# EEG-RM_170118P02.net
KiCad netlist of a schematic drawn in EAGLE
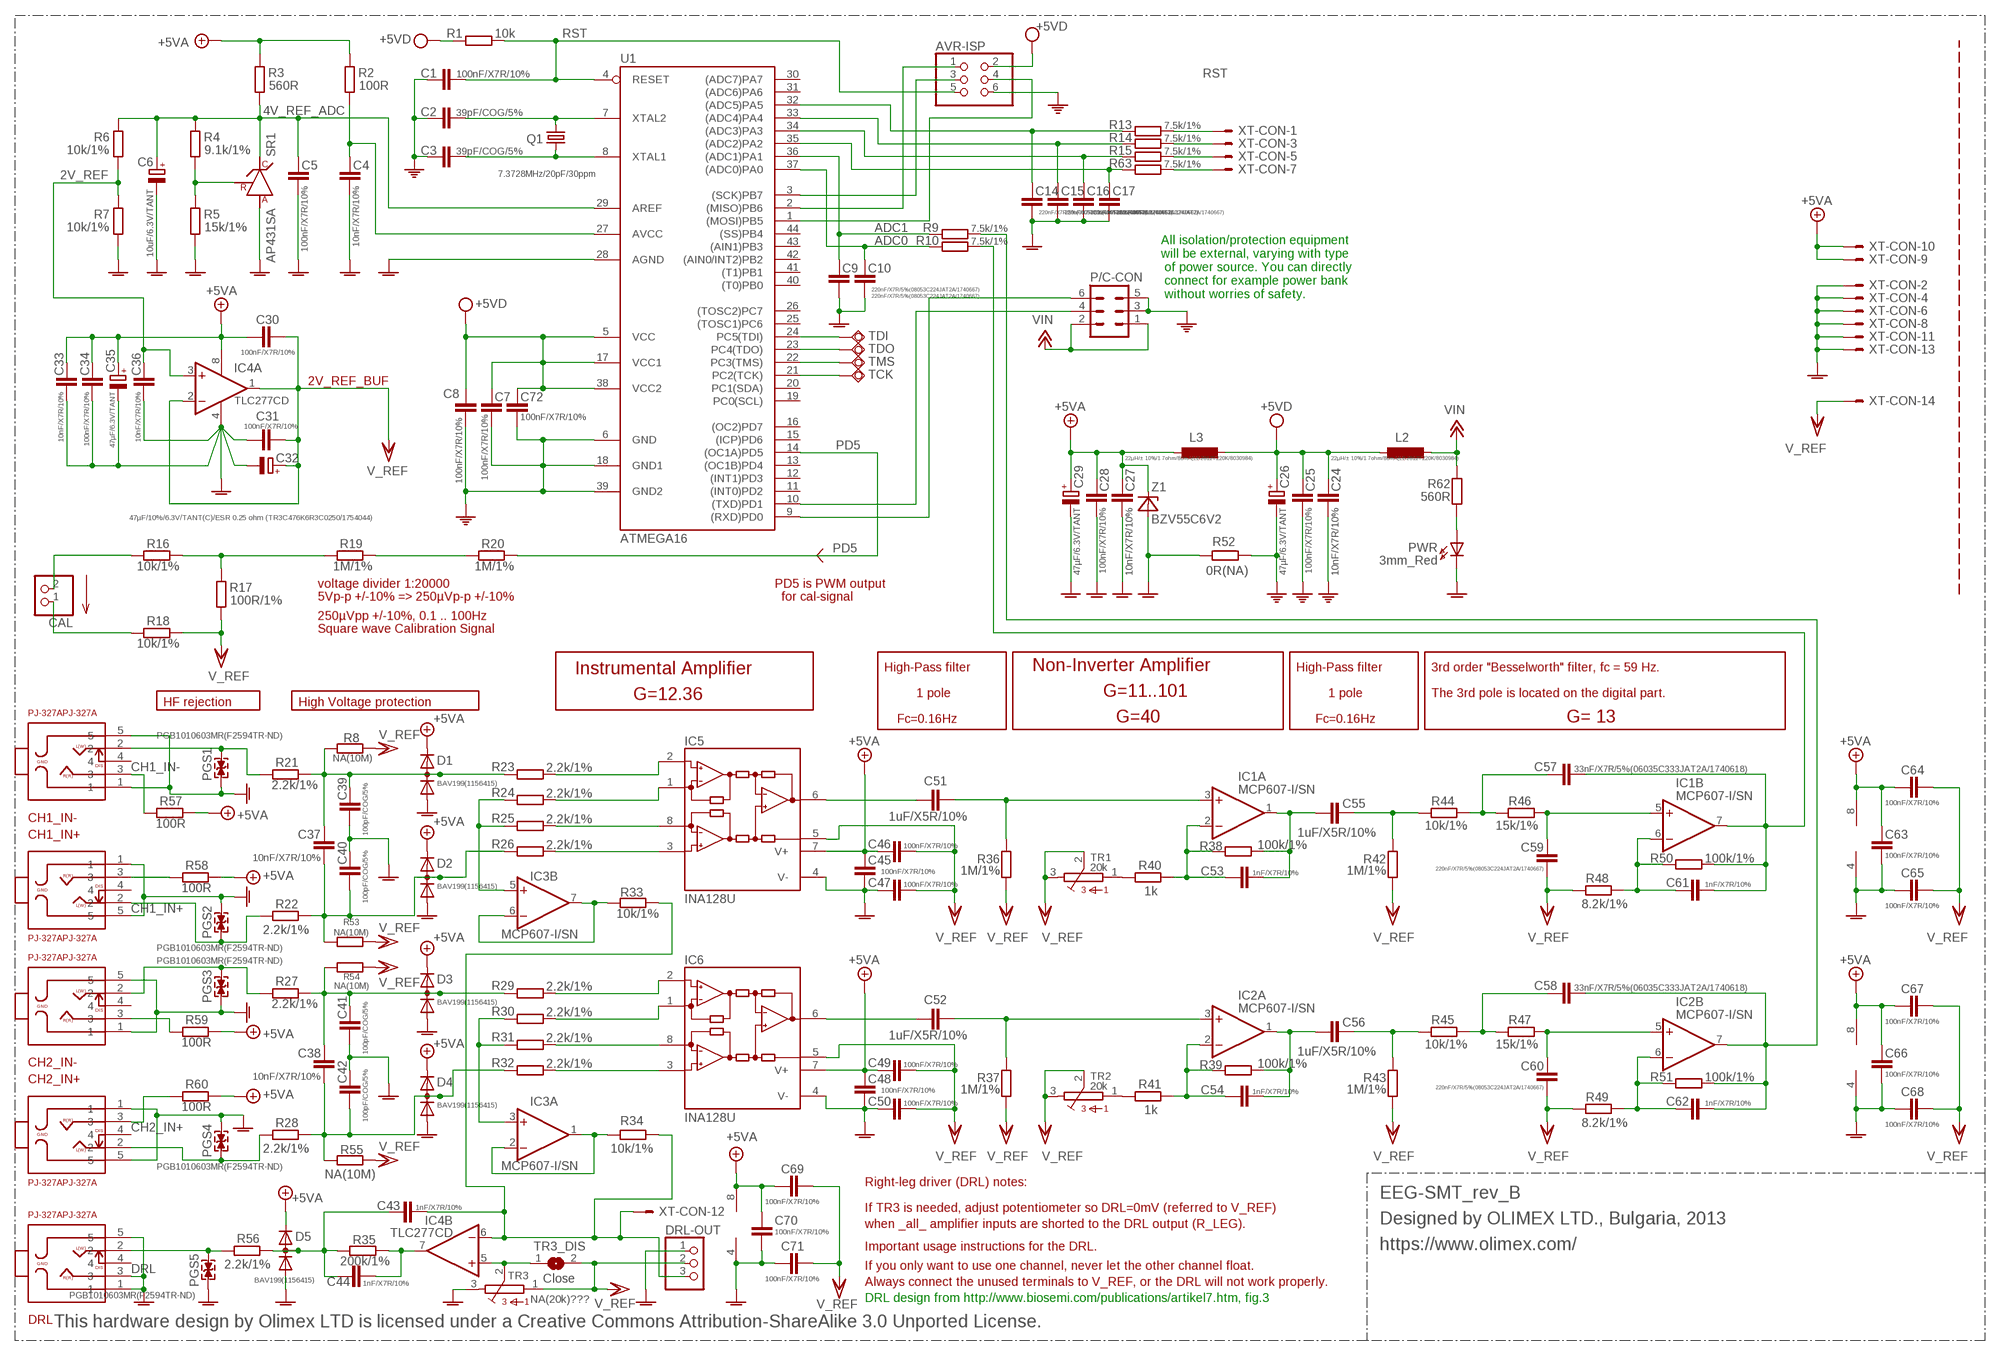
[diagram p0: schematic, sheet 1]

(export (version "E")
  (design (tool "Eeschema 10.0.6"))
  (components
    (comp (ref "AVR-ISP")
      (value "PINHD-2X3")
      (footprint "eagle-import:2X03")
      (libsource (lib "eagle-import") (part "PINHD-2X3"))
    )
    (comp (ref "C1")
      (value "100nF/X7R/10%")
      (footprint "eagle-import:C0603")
      (libsource (lib "eagle-import") (part "C-EUC0603"))
    )
    (comp (ref "C2")
      (value "39pF/COG/5%")
      (footprint "eagle-import:C0603")
      (libsource (lib "eagle-import") (part "C-EUC0603"))
    )
    (comp (ref "C3")
      (value "39pF/COG/5%")
      (footprint "eagle-import:C0603")
      (libsource (lib "eagle-import") (part "C-EUC0603"))
    )
    (comp (ref "C4")
      (value "10nF/X7R/10%")
      (footprint "eagle-import:C0603")
      (libsource (lib "eagle-import") (part "C-EUC0603"))
    )
    (comp (ref "C5")
      (value "100nF/X7R/10%")
      (footprint "eagle-import:C0603")
      (libsource (lib "eagle-import") (part "C-EUC0603"))
    )
    (comp (ref "C6")
      (value "10uF/6.3V/TANT")
      (footprint "eagle-import:CT3216")
      (libsource (lib "eagle-import") (part "CPOL-EUCT3216"))
    )
    (comp (ref "C7")
      (value "100nF/X7R/10%")
      (footprint "eagle-import:C0603")
      (libsource (lib "eagle-import") (part "C-EUC0603"))
    )
    (comp (ref "C8")
      (value "100nF/X7R/10%")
      (footprint "eagle-import:C0603")
      (libsource (lib "eagle-import") (part "C-EUC0603"))
    )
    (comp (ref "C9")
      (value "220nF/X7R/5%(08053C224JAT2A/1740667)")
      (footprint "eagle-import:C0603")
      (libsource (lib "eagle-import") (part "C-EUC0603"))
    )
    (comp (ref "C10")
      (value "220nF/X7R/5%(08053C224JAT2A/1740667)")
      (footprint "eagle-import:C0603")
      (libsource (lib "eagle-import") (part "C-EUC0603"))
    )
    (comp (ref "C14")
      (value "220nF/X7R/5%(08053C224JAT2A/1740667)")
      (footprint "eagle-import:C0603")
      (libsource (lib "eagle-import") (part "C-EUC0603"))
    )
    (comp (ref "C15")
      (value "220nF/X7R/5%(08053C224JAT2A/1740667)")
      (footprint "eagle-import:C0603")
      (libsource (lib "eagle-import") (part "C-EUC0603"))
    )
    (comp (ref "C16")
      (value "220nF/X7R/5%(08053C224JAT2A/1740667)")
      (footprint "eagle-import:C0603")
      (libsource (lib "eagle-import") (part "C-EUC0603"))
    )
    (comp (ref "C17")
      (value "220nF/X7R/5%(08053C224JAT2A/1740667)")
      (footprint "eagle-import:C0603")
      (libsource (lib "eagle-import") (part "C-EUC0603"))
    )
    (comp (ref "C24")
      (value "10nF/X7R/10%")
      (footprint "eagle-import:C0603")
      (libsource (lib "eagle-import") (part "C-EUC0603"))
    )
    (comp (ref "C25")
      (value "100nF/X7R/10%")
      (footprint "eagle-import:C0603")
      (libsource (lib "eagle-import") (part "C-EUC0603"))
    )
    (comp (ref "C26")
      (value "47µF/6.3V/TANT")
      (footprint "eagle-import:CT3216")
      (libsource (lib "eagle-import") (part "CPOL-EUCT3216"))
    )
    (comp (ref "C27")
      (value "10nF/X7R/10%")
      (footprint "eagle-import:C0603")
      (libsource (lib "eagle-import") (part "C-EUC0603"))
    )
    (comp (ref "C28")
      (value "100nF/X7R/10%")
      (footprint "eagle-import:C0603")
      (libsource (lib "eagle-import") (part "C-EUC0603"))
    )
    (comp (ref "C29")
      (value "47µF/6.3V/TANT")
      (footprint "eagle-import:CT3216")
      (libsource (lib "eagle-import") (part "CPOL-EUCT3216"))
    )
    (comp (ref "C30")
      (value "100nF/X7R/10%")
      (footprint "eagle-import:C0603")
      (libsource (lib "eagle-import") (part "C-EUC0603"))
    )
    (comp (ref "C31")
      (value "100nF/X7R/10%")
      (footprint "eagle-import:C0603")
      (libsource (lib "eagle-import") (part "C-EUC0603"))
    )
    (comp (ref "C32")
      (value "47µF/10%/6.3V/TANT(C)/ESR 0.25 ohm (TR3C476K6R3C0250/1754044)")
      (footprint "eagle-import:CT3528")
      (libsource (lib "eagle-import") (part "CPOL-EUCT3528"))
    )
    (comp (ref "C33")
      (value "10nF/X7R/10%")
      (footprint "eagle-import:C0603")
      (libsource (lib "eagle-import") (part "C-EUC0603"))
    )
    (comp (ref "C34")
      (value "100nF/X7R/10%")
      (footprint "eagle-import:C0603")
      (libsource (lib "eagle-import") (part "C-EUC0603"))
    )
    (comp (ref "C35")
      (value "47µF/6.3V/TANT")
      (footprint "eagle-import:CT3216")
      (libsource (lib "eagle-import") (part "CPOL-EUCT3216"))
    )
    (comp (ref "C36")
      (value "10nF/X7R/10%")
      (footprint "eagle-import:C0603")
      (libsource (lib "eagle-import") (part "C-EUC0603"))
    )
    (comp (ref "C37")
      (value "10nF/X7R/10%")
      (footprint "eagle-import:C0603")
      (libsource (lib "eagle-import") (part "C-EUC0603"))
    )
    (comp (ref "C38")
      (value "10nF/X7R/10%")
      (footprint "eagle-import:C0603")
      (libsource (lib "eagle-import") (part "C-EUC0603"))
    )
    (comp (ref "C39")
      (value "100pF/COG/5%")
      (footprint "eagle-import:C0603")
      (libsource (lib "eagle-import") (part "C-EUC0603"))
    )
    (comp (ref "C40")
      (value "100pF/COG/5%")
      (footprint "eagle-import:C0603")
      (libsource (lib "eagle-import") (part "C-EUC0603"))
    )
    (comp (ref "C41")
      (value "100pF/COG/5%")
      (footprint "eagle-import:C0603")
      (libsource (lib "eagle-import") (part "C-EUC0603"))
    )
    (comp (ref "C42")
      (value "100pF/COG/5%")
      (footprint "eagle-import:C0603")
      (libsource (lib "eagle-import") (part "C-EUC0603"))
    )
    (comp (ref "C43")
      (value "1nF/X7R/10%")
      (footprint "eagle-import:C0603")
      (libsource (lib "eagle-import") (part "C-EUC0603"))
    )
    (comp (ref "C44")
      (value "1nF/X7R/10%")
      (footprint "eagle-import:C0603")
      (libsource (lib "eagle-import") (part "C-EUC0603"))
    )
    (comp (ref "C45")
      (value "100nF/X7R/10%")
      (footprint "eagle-import:C0603")
      (libsource (lib "eagle-import") (part "C-EUC0603"))
    )
    (comp (ref "C46")
      (value "100nF/X7R/10%")
      (footprint "eagle-import:C0603")
      (libsource (lib "eagle-import") (part "C-EUC0603"))
    )
    (comp (ref "C47")
      (value "100nF/X7R/10%")
      (footprint "eagle-import:C0603")
      (libsource (lib "eagle-import") (part "C-EUC0603"))
    )
    (comp (ref "C48")
      (value "100nF/X7R/10%")
      (footprint "eagle-import:C0603")
      (libsource (lib "eagle-import") (part "C-EUC0603"))
    )
    (comp (ref "C49")
      (value "100nF/X7R/10%")
      (footprint "eagle-import:C0603")
      (libsource (lib "eagle-import") (part "C-EUC0603"))
    )
    (comp (ref "C50")
      (value "100nF/X7R/10%")
      (footprint "eagle-import:C0603")
      (libsource (lib "eagle-import") (part "C-EUC0603"))
    )
    (comp (ref "C51")
      (value "1uF/X5R/10%")
      (footprint "eagle-import:C0603")
      (libsource (lib "eagle-import") (part "C-EUC0603"))
    )
    (comp (ref "C52")
      (value "1uF/X5R/10%")
      (footprint "eagle-import:C0603")
      (libsource (lib "eagle-import") (part "C-EUC0603"))
    )
    (comp (ref "C53")
      (value "1nF/X7R/10%")
      (footprint "eagle-import:C0603")
      (libsource (lib "eagle-import") (part "C-EUC0603"))
    )
    (comp (ref "C54")
      (value "1nF/X7R/10%")
      (footprint "eagle-import:C0603")
      (libsource (lib "eagle-import") (part "C-EUC0603"))
    )
    (comp (ref "C55")
      (value "1uF/X5R/10%")
      (footprint "eagle-import:C0603")
      (libsource (lib "eagle-import") (part "C-EUC0603"))
    )
    (comp (ref "C56")
      (value "1uF/X5R/10%")
      (footprint "eagle-import:C0603")
      (libsource (lib "eagle-import") (part "C-EUC0603"))
    )
    (comp (ref "C57")
      (value "33nF/X7R/5%(06035C333JAT2A/1740618)")
      (footprint "eagle-import:C0603")
      (libsource (lib "eagle-import") (part "C-EUC0603"))
    )
    (comp (ref "C58")
      (value "33nF/X7R/5%(06035C333JAT2A/1740618)")
      (footprint "eagle-import:C0603")
      (libsource (lib "eagle-import") (part "C-EUC0603"))
    )
    (comp (ref "C59")
      (value "220nF/X7R/5%(08053C224JAT2A/1740667)")
      (footprint "eagle-import:C0603")
      (libsource (lib "eagle-import") (part "C-EUC0603"))
    )
    (comp (ref "C60")
      (value "220nF/X7R/5%(08053C224JAT2A/1740667)")
      (footprint "eagle-import:C0603")
      (libsource (lib "eagle-import") (part "C-EUC0603"))
    )
    (comp (ref "C61")
      (value "1nF/X7R/10%")
      (footprint "eagle-import:C0603")
      (libsource (lib "eagle-import") (part "C-EUC0603"))
    )
    (comp (ref "C62")
      (value "1nF/X7R/10%")
      (footprint "eagle-import:C0603")
      (libsource (lib "eagle-import") (part "C-EUC0603"))
    )
    (comp (ref "C63")
      (value "100nF/X7R/10%")
      (footprint "eagle-import:C0603")
      (libsource (lib "eagle-import") (part "C-EUC0603"))
    )
    (comp (ref "C64")
      (value "100nF/X7R/10%")
      (footprint "eagle-import:C0603")
      (libsource (lib "eagle-import") (part "C-EUC0603"))
    )
    (comp (ref "C65")
      (value "100nF/X7R/10%")
      (footprint "eagle-import:C0603")
      (libsource (lib "eagle-import") (part "C-EUC0603"))
    )
    (comp (ref "C66")
      (value "100nF/X7R/10%")
      (footprint "eagle-import:C0603")
      (libsource (lib "eagle-import") (part "C-EUC0603"))
    )
    (comp (ref "C67")
      (value "100nF/X7R/10%")
      (footprint "eagle-import:C0603")
      (libsource (lib "eagle-import") (part "C-EUC0603"))
    )
    (comp (ref "C68")
      (value "100nF/X7R/10%")
      (footprint "eagle-import:C0603")
      (libsource (lib "eagle-import") (part "C-EUC0603"))
    )
    (comp (ref "C69")
      (value "100nF/X7R/10%")
      (footprint "eagle-import:C0603")
      (libsource (lib "eagle-import") (part "C-EUC0603"))
    )
    (comp (ref "C70")
      (value "100nF/X7R/10%")
      (footprint "eagle-import:C0603")
      (libsource (lib "eagle-import") (part "C-EUC0603"))
    )
    (comp (ref "C71")
      (value "100nF/X7R/10%")
      (footprint "eagle-import:C0603")
      (libsource (lib "eagle-import") (part "C-EUC0603"))
    )
    (comp (ref "C72")
      (value "100nF/X7R/10%")
      (footprint "eagle-import:C0603")
      (libsource (lib "eagle-import") (part "C-EUC0603"))
    )
    (comp (ref "CAL")
      (value "PINHD-1X2")
      (footprint "eagle-import:1X02")
      (libsource (lib "eagle-import") (part "PINHD-1X2"))
    )
    (comp (ref "CH1_IN+")
      (value "PJ-327APJ-327A")
      (footprint "eagle-import:PJ-327A")
      (libsource (lib "eagle-import") (part "PJ-327APJ-327A"))
    )
    (comp (ref "CH1_IN-")
      (value "PJ-327APJ-327A")
      (footprint "eagle-import:PJ-327A")
      (libsource (lib "eagle-import") (part "PJ-327APJ-327A"))
    )
    (comp (ref "CH2_IN+")
      (value "PJ-327APJ-327A")
      (footprint "eagle-import:PJ-327A")
      (libsource (lib "eagle-import") (part "PJ-327APJ-327A"))
    )
    (comp (ref "CH2_IN-")
      (value "PJ-327APJ-327A")
      (footprint "eagle-import:PJ-327A")
      (libsource (lib "eagle-import") (part "PJ-327APJ-327A"))
    )
    (comp (ref "D1")
      (value "BAV199(1156415)")
      (footprint "eagle-import:SOT23C")
      (libsource (lib "eagle-import") (part "DIODE_AC-AC__"))
    )
    (comp (ref "D2")
      (value "BAV199(1156415)")
      (footprint "eagle-import:SOT23C")
      (libsource (lib "eagle-import") (part "DIODE_AC-AC__"))
    )
    (comp (ref "D3")
      (value "BAV199(1156415)")
      (footprint "eagle-import:SOT23C")
      (libsource (lib "eagle-import") (part "DIODE_AC-AC__"))
    )
    (comp (ref "D4")
      (value "BAV199(1156415)")
      (footprint "eagle-import:SOT23C")
      (libsource (lib "eagle-import") (part "DIODE_AC-AC__"))
    )
    (comp (ref "D5")
      (value "BAV199(1156415)")
      (footprint "eagle-import:SOT23C")
      (libsource (lib "eagle-import") (part "DIODE_AC-AC__"))
    )
    (comp (ref "DRL")
      (value "PJ-327APJ-327A")
      (footprint "eagle-import:PJ-327A")
      (libsource (lib "eagle-import") (part "PJ-327APJ-327A"))
    )
    (comp (ref "DRL-OUT")
      (value "PINHD-1X3")
      (footprint "eagle-import:1X03")
      (libsource (lib "eagle-import") (part "PINHD-1X3"))
    )
    (comp (ref "IC1")
      (value "MCP607-I/SN")
      (footprint "eagle-import:SO08")
      (libsource (lib "eagle-import") (part "LM358D"))
    )
    (comp (ref "IC2")
      (value "MCP607-I/SN")
      (footprint "eagle-import:SO08")
      (libsource (lib "eagle-import") (part "LM358D"))
    )
    (comp (ref "IC3")
      (value "MCP607-I/SN")
      (footprint "eagle-import:SO08")
      (libsource (lib "eagle-import") (part "LM358D"))
    )
    (comp (ref "IC4")
      (value "TLC277CD")
      (footprint "eagle-import:SO08")
      (libsource (lib "eagle-import") (part "LM358D"))
    )
    (comp (ref "IC5")
      (value "INA128U")
      (footprint "eagle-import:SO08")
      (fields (field (name "MF") "TEXAS INSTRUMENTS"))
      (libsource (lib "eagle-import") (part "INA128U"))
    )
    (comp (ref "IC6")
      (value "INA128U")
      (footprint "eagle-import:SO08")
      (fields (field (name "MF") "TEXAS INSTRUMENTS"))
      (libsource (lib "eagle-import") (part "INA128U"))
    )
    (comp (ref "L2")
      (value "22µH/± 10%/1.7ohm/80mA(LB2012T220K/8030984)")
      (footprint "eagle-import:L2012C")
      (libsource (lib "eagle-import") (part "L-EUL2012C"))
    )
    (comp (ref "L3")
      (value "22µH/± 10%/1.7ohm/80mA(LB2012T220K/8030984)")
      (footprint "eagle-import:L2012C")
      (libsource (lib "eagle-import") (part "L-EUL2012C"))
    )
    (comp (ref "P/C-CON")
      (value "ML6L")
      (footprint "eagle-import:ML6L")
      (libsource (lib "eagle-import") (part "ML6L"))
    )
    (comp (ref "PGS1")
      (value "PGB1010603MR(F2594TR-ND)")
      (footprint "eagle-import:0603")
      (libsource (lib "eagle-import") (part "PGB1010603MR(F2594TR-ND)"))
    )
    (comp (ref "PGS2")
      (value "PGB1010603MR(F2594TR-ND)")
      (footprint "eagle-import:0603")
      (libsource (lib "eagle-import") (part "PGB1010603MR(F2594TR-ND)"))
    )
    (comp (ref "PGS3")
      (value "PGB1010603MR(F2594TR-ND)")
      (footprint "eagle-import:0603")
      (libsource (lib "eagle-import") (part "PGB1010603MR(F2594TR-ND)"))
    )
    (comp (ref "PGS4")
      (value "PGB1010603MR(F2594TR-ND)")
      (footprint "eagle-import:0603")
      (libsource (lib "eagle-import") (part "PGB1010603MR(F2594TR-ND)"))
    )
    (comp (ref "PGS5")
      (value "PGB1010603MR(F2594TR-ND)")
      (footprint "eagle-import:0603")
      (libsource (lib "eagle-import") (part "PGB1010603MR(F2594TR-ND)"))
    )
    (comp (ref "PWR")
      (value "3mm_Red")
      (footprint "eagle-import:LED-3.0MM")
      (libsource (lib "eagle-import") (part "LED3.0MM"))
    )
    (comp (ref "Q1")
      (value "7.3728MHz/20pF/30ppm")
      (footprint "eagle-import:HC49_SMD2_THIN")
      (libsource (lib "eagle-import") (part "HC49/S1"))
    )
    (comp (ref "R1")
      (value "10k")
      (footprint "eagle-import:R0603")
      (libsource (lib "eagle-import") (part "R-EU_R0603"))
    )
    (comp (ref "R2")
      (value "100R")
      (footprint "eagle-import:R0603")
      (libsource (lib "eagle-import") (part "R-EU_R0603"))
    )
    (comp (ref "R3")
      (value "560R")
      (footprint "eagle-import:R0603")
      (libsource (lib "eagle-import") (part "R-EU_R0603"))
    )
    (comp (ref "R4")
      (value "9.1k/1%")
      (footprint "eagle-import:R0603")
      (libsource (lib "eagle-import") (part "R-EU_R0603"))
    )
    (comp (ref "R5")
      (value "15k/1%")
      (footprint "eagle-import:R0603")
      (libsource (lib "eagle-import") (part "R-EU_R0603"))
    )
    (comp (ref "R6")
      (value "10k/1%")
      (footprint "eagle-import:R0603")
      (libsource (lib "eagle-import") (part "R-EU_R0603"))
    )
    (comp (ref "R7")
      (value "10k/1%")
      (footprint "eagle-import:R0603")
      (libsource (lib "eagle-import") (part "R-EU_R0603"))
    )
    (comp (ref "R8")
      (value "NA(10M)")
      (footprint "eagle-import:R0603")
      (libsource (lib "eagle-import") (part "R-EU_R0603"))
    )
    (comp (ref "R9")
      (value "7.5k/1%")
      (footprint "eagle-import:M2012")
      (libsource (lib "eagle-import") (part "R-EU_M2012"))
    )
    (comp (ref "R10")
      (value "7.5k/1%")
      (footprint "eagle-import:M2012")
      (libsource (lib "eagle-import") (part "R-EU_M2012"))
    )
    (comp (ref "R13")
      (value "7.5k/1%")
      (footprint "eagle-import:M2012")
      (libsource (lib "eagle-import") (part "R-EU_M2012"))
    )
    (comp (ref "R14")
      (value "7.5k/1%")
      (footprint "eagle-import:M2012")
      (libsource (lib "eagle-import") (part "R-EU_M2012"))
    )
    (comp (ref "R15")
      (value "7.5k/1%")
      (footprint "eagle-import:M2012")
      (libsource (lib "eagle-import") (part "R-EU_M2012"))
    )
    (comp (ref "R16")
      (value "10k/1%")
      (footprint "eagle-import:R0603")
      (libsource (lib "eagle-import") (part "R-EU_R0603"))
    )
    (comp (ref "R17")
      (value "100R/1%")
      (footprint "eagle-import:R0603")
      (libsource (lib "eagle-import") (part "R-EU_R0603"))
    )
    (comp (ref "R18")
      (value "10k/1%")
      (footprint "eagle-import:R0603")
      (libsource (lib "eagle-import") (part "R-EU_R0603"))
    )
    (comp (ref "R19")
      (value "1M/1%")
      (footprint "eagle-import:R0603")
      (libsource (lib "eagle-import") (part "R-EU_R0603"))
    )
    (comp (ref "R20")
      (value "1M/1%")
      (footprint "eagle-import:R0603")
      (libsource (lib "eagle-import") (part "R-EU_R0603"))
    )
    (comp (ref "R21")
      (value "2.2k/1%")
      (footprint "eagle-import:R0603")
      (libsource (lib "eagle-import") (part "R-EU_R0603"))
    )
    (comp (ref "R22")
      (value "2.2k/1%")
      (footprint "eagle-import:R0603")
      (libsource (lib "eagle-import") (part "R-EU_R0603"))
    )
    (comp (ref "R23")
      (value "2.2k/1%")
      (footprint "eagle-import:R0603")
      (libsource (lib "eagle-import") (part "R-EU_R0603"))
    )
    (comp (ref "R24")
      (value "2.2k/1%")
      (footprint "eagle-import:R0603")
      (libsource (lib "eagle-import") (part "R-EU_R0603"))
    )
    (comp (ref "R25")
      (value "2.2k/1%")
      (footprint "eagle-import:R0603")
      (libsource (lib "eagle-import") (part "R-EU_R0603"))
    )
    (comp (ref "R26")
      (value "2.2k/1%")
      (footprint "eagle-import:R0603")
      (libsource (lib "eagle-import") (part "R-EU_R0603"))
    )
    (comp (ref "R27")
      (value "2.2k/1%")
      (footprint "eagle-import:R0603")
      (libsource (lib "eagle-import") (part "R-EU_R0603"))
    )
    (comp (ref "R28")
      (value "2.2k/1%")
      (footprint "eagle-import:R0603")
      (libsource (lib "eagle-import") (part "R-EU_R0603"))
    )
    (comp (ref "R29")
      (value "2.2k/1%")
      (footprint "eagle-import:R0603")
      (libsource (lib "eagle-import") (part "R-EU_R0603"))
    )
    (comp (ref "R30")
      (value "2.2k/1%")
      (footprint "eagle-import:R0603")
      (libsource (lib "eagle-import") (part "R-EU_R0603"))
    )
    (comp (ref "R31")
      (value "2.2k/1%")
      (footprint "eagle-import:R0603")
      (libsource (lib "eagle-import") (part "R-EU_R0603"))
    )
    (comp (ref "R32")
      (value "2.2k/1%")
      (footprint "eagle-import:R0603")
      (libsource (lib "eagle-import") (part "R-EU_R0603"))
    )
    (comp (ref "R33")
      (value "10k/1%")
      (footprint "eagle-import:R0603")
      (libsource (lib "eagle-import") (part "R-EU_R0603"))
    )
    (comp (ref "R34")
      (value "10k/1%")
      (footprint "eagle-import:R0603")
      (libsource (lib "eagle-import") (part "R-EU_R0603"))
    )
    (comp (ref "R35")
      (value "200k/1%")
      (footprint "eagle-import:R0603")
      (libsource (lib "eagle-import") (part "R-EU_R0603"))
    )
    (comp (ref "R36")
      (value "1M/1%")
      (footprint "eagle-import:R0603")
      (libsource (lib "eagle-import") (part "R-EU_R0603"))
    )
    (comp (ref "R37")
      (value "1M/1%")
      (footprint "eagle-import:R0603")
      (libsource (lib "eagle-import") (part "R-EU_R0603"))
    )
    (comp (ref "R38")
      (value "100k/1%")
      (footprint "eagle-import:R0603")
      (libsource (lib "eagle-import") (part "R-EU_R0603"))
    )
    (comp (ref "R39")
      (value "100k/1%")
      (footprint "eagle-import:R0603")
      (libsource (lib "eagle-import") (part "R-EU_R0603"))
    )
    (comp (ref "R40")
      (value "1k")
      (footprint "eagle-import:R0603")
      (libsource (lib "eagle-import") (part "R-EU_R0603"))
    )
    (comp (ref "R41")
      (value "1k")
      (footprint "eagle-import:R0603")
      (libsource (lib "eagle-import") (part "R-EU_R0603"))
    )
    (comp (ref "R42")
      (value "1M/1%")
      (footprint "eagle-import:R0603")
      (libsource (lib "eagle-import") (part "R-EU_R0603"))
    )
    (comp (ref "R43")
      (value "1M/1%")
      (footprint "eagle-import:R0603")
      (libsource (lib "eagle-import") (part "R-EU_R0603"))
    )
    (comp (ref "R44")
      (value "10k/1%")
      (footprint "eagle-import:R0603")
      (libsource (lib "eagle-import") (part "R-EU_R0603"))
    )
    (comp (ref "R45")
      (value "10k/1%")
      (footprint "eagle-import:R0603")
      (libsource (lib "eagle-import") (part "R-EU_R0603"))
    )
    (comp (ref "R46")
      (value "15k/1%")
      (footprint "eagle-import:R0603")
      (libsource (lib "eagle-import") (part "R-EU_R0603"))
    )
    (comp (ref "R47")
      (value "15k/1%")
      (footprint "eagle-import:R0603")
      (libsource (lib "eagle-import") (part "R-EU_R0603"))
    )
    (comp (ref "R48")
      (value "8.2k/1%")
      (footprint "eagle-import:R0603")
      (libsource (lib "eagle-import") (part "R-EU_R0603"))
    )
    (comp (ref "R49")
      (value "8.2k/1%")
      (footprint "eagle-import:R0603")
      (libsource (lib "eagle-import") (part "R-EU_R0603"))
    )
    (comp (ref "R50")
      (value "100k/1%")
      (footprint "eagle-import:R0603")
      (libsource (lib "eagle-import") (part "R-EU_R0603"))
    )
    (comp (ref "R51")
      (value "100k/1%")
      (footprint "eagle-import:R0603")
      (libsource (lib "eagle-import") (part "R-EU_R0603"))
    )
    (comp (ref "R52")
      (value "0R(NA)")
      (footprint "eagle-import:R0603")
      (libsource (lib "eagle-import") (part "R-EU_R0603"))
    )
    (comp (ref "R53")
      (value "NA(10M)")
      (footprint "eagle-import:R0603")
      (libsource (lib "eagle-import") (part "R-EU_R0603"))
    )
    (comp (ref "R54")
      (value "NA(10M)")
      (footprint "eagle-import:R0603")
      (libsource (lib "eagle-import") (part "R-EU_R0603"))
    )
    (comp (ref "R55")
      (value "NA(10M)")
      (footprint "eagle-import:R0603")
      (libsource (lib "eagle-import") (part "R-EU_R0603"))
    )
    (comp (ref "R56")
      (value "2.2k/1%")
      (footprint "eagle-import:R0603")
      (libsource (lib "eagle-import") (part "R-EU_R0603"))
    )
    (comp (ref "R57")
      (value "100R")
      (footprint "eagle-import:R0603")
      (libsource (lib "eagle-import") (part "R-EU_R0603"))
    )
    (comp (ref "R58")
      (value "100R")
      (footprint "eagle-import:R0603")
      (libsource (lib "eagle-import") (part "R-EU_R0603"))
    )
    (comp (ref "R59")
      (value "100R")
      (footprint "eagle-import:R0603")
      (libsource (lib "eagle-import") (part "R-EU_R0603"))
    )
    (comp (ref "R60")
      (value "100R")
      (footprint "eagle-import:R0603")
      (libsource (lib "eagle-import") (part "R-EU_R0603"))
    )
    (comp (ref "R62")
      (value "560R")
      (footprint "eagle-import:R0603")
      (libsource (lib "eagle-import") (part "R-EU_R0603"))
    )
    (comp (ref "R63")
      (value "7.5k/1%")
      (footprint "eagle-import:M2012")
      (libsource (lib "eagle-import") (part "R-EU_M2012"))
    )
    (comp (ref "SR1")
      (value "AP431SA")
      (footprint "eagle-import:SOT-23")
      (libsource (lib "eagle-import") (part "TL431'''"))
    )
    (comp (ref "TCK")
      (value "TESTPAD80/30")
      (footprint "eagle-import:SMD80_30")
      (libsource (lib "eagle-import") (part "TESTPAD80/30"))
    )
    (comp (ref "TDI")
      (value "TESTPAD80/30")
      (footprint "eagle-import:SMD80_30")
      (libsource (lib "eagle-import") (part "TESTPAD80/30"))
    )
    (comp (ref "TDO")
      (value "TESTPAD80/30")
      (footprint "eagle-import:SMD80_30")
      (libsource (lib "eagle-import") (part "TESTPAD80/30"))
    )
    (comp (ref "TMS")
      (value "TESTPAD80/30")
      (footprint "eagle-import:SMD80_30")
      (libsource (lib "eagle-import") (part "TESTPAD80/30"))
    )
    (comp (ref "TR1")
      (value "20k")
      (footprint "eagle-import:S64Y")
      (libsource (lib "eagle-import") (part "S64Y"))
    )
    (comp (ref "TR2")
      (value "20k")
      (footprint "eagle-import:S64Y")
      (libsource (lib "eagle-import") (part "S64Y"))
    )
    (comp (ref "TR3")
      (value "NA(20k)???")
      (footprint "eagle-import:S64Y")
      (libsource (lib "eagle-import") (part "S64Y"))
    )
    (comp (ref "TR3_DIS")
      (value "Close")
      (footprint "eagle-import:SJ_1_SMALLER")
      (libsource (lib "eagle-import") (part "SJSJ_SMALLER"))
    )
    (comp (ref "U1")
      (value "ATMEGA16")
      (footprint "eagle-import:44TQFP")
      (libsource (lib "eagle-import") (part "ATMEGA16"))
    )
    (comp (ref "XT-CON")
      (value "ML14LE")
      (footprint "eagle-import:ML14L")
      (libsource (lib "eagle-import") (part "ML14?EL"))
    )
    (comp (ref "Z1")
      (value "BZV55C6V2")
      (footprint "eagle-import:MINI-MELF")
      (libsource (lib "eagle-import") (part "ZDIOD-SMD"))
    )
  )
  (nets
    (net (code "1") (name "+5VA") (class "Default")
      (node (ref "C27") (pin "1") (pinfunction "1_1") (pintype "passive"))
      (node (ref "C28") (pin "1") (pinfunction "1_1") (pintype "passive"))
      (node (ref "C29") (pin "+") (pinfunction "+_+") (pintype "passive"))
      (node (ref "C30") (pin "2") (pinfunction "2_2") (pintype "passive"))
      (node (ref "C33") (pin "1") (pinfunction "1_1") (pintype "passive"))
      (node (ref "C34") (pin "1") (pinfunction "1_1") (pintype "passive"))
      (node (ref "C35") (pin "+") (pinfunction "+_+") (pintype "passive"))
      (node (ref "C45") (pin "1") (pinfunction "1_1") (pintype "passive"))
      (node (ref "C46") (pin "1") (pinfunction "1_1") (pintype "passive"))
      (node (ref "C48") (pin "1") (pinfunction "1_1") (pintype "passive"))
      (node (ref "C49") (pin "1") (pinfunction "1_1") (pintype "passive"))
      (node (ref "C63") (pin "1") (pinfunction "1_1") (pintype "passive"))
      (node (ref "C64") (pin "1") (pinfunction "1_1") (pintype "passive"))
      (node (ref "C66") (pin "1") (pinfunction "1_1") (pintype "passive"))
      (node (ref "C67") (pin "1") (pinfunction "1_1") (pintype "passive"))
      (node (ref "C69") (pin "1") (pinfunction "1_1") (pintype "passive"))
      (node (ref "C70") (pin "1") (pinfunction "1_1") (pintype "passive"))
      (node (ref "D1") (pin "1") (pinfunction "K_1") (pintype "passive"))
      (node (ref "D2") (pin "1") (pinfunction "K_1") (pintype "passive"))
      (node (ref "D3") (pin "1") (pinfunction "K_1") (pintype "passive"))
      (node (ref "D4") (pin "1") (pinfunction "K_1") (pintype "passive"))
      (node (ref "D5") (pin "1") (pinfunction "K_1") (pintype "passive"))
      (node (ref "IC1") (pin "8") (pinfunction "V+_8") (pintype "power_in"))
      (node (ref "IC2") (pin "8") (pinfunction "V+_8") (pintype "power_in"))
      (node (ref "IC3") (pin "8") (pinfunction "V+_8") (pintype "power_in"))
      (node (ref "IC4") (pin "8") (pinfunction "V+_8") (pintype "power_in"))
      (node (ref "IC5") (pin "7") (pinfunction "V+_7") (pintype "power_in"))
      (node (ref "IC6") (pin "7") (pinfunction "V+_7") (pintype "power_in"))
      (node (ref "L3") (pin "2") (pinfunction "2_2") (pintype "passive"))
      (node (ref "R2") (pin "2") (pinfunction "2_2") (pintype "passive"))
      (node (ref "R3") (pin "2") (pinfunction "2_2") (pintype "passive"))
      (node (ref "R57") (pin "2") (pinfunction "2_2") (pintype "passive"))
      (node (ref "R58") (pin "2") (pinfunction "2_2") (pintype "passive"))
      (node (ref "R59") (pin "2") (pinfunction "2_2") (pintype "passive"))
      (node (ref "R60") (pin "2") (pinfunction "2_2") (pintype "passive"))
      (node (ref "XT-CON") (pin "10") (pinfunction "S_10") (pintype "passive"))
      (node (ref "XT-CON") (pin "9") (pinfunction "S_9") (pintype "passive"))
      (node (ref "Z1") (pin "1") (pinfunction "C_1") (pintype "passive"))
    )
    (net (code "2") (name "+5VD") (class "Default")
      (node (ref "AVR-ISP") (pin "2") (pinfunction "2_2") (pintype "passive"))
      (node (ref "C24") (pin "1") (pinfunction "1_1") (pintype "passive"))
      (node (ref "C25") (pin "1") (pinfunction "1_1") (pintype "passive"))
      (node (ref "C26") (pin "+") (pinfunction "+_+") (pintype "passive"))
      (node (ref "C7") (pin "1") (pinfunction "1_1") (pintype "passive"))
      (node (ref "C72") (pin "1") (pinfunction "1_1") (pintype "passive"))
      (node (ref "C8") (pin "1") (pinfunction "1_1") (pintype "passive"))
      (node (ref "L2") (pin "2") (pinfunction "2_2") (pintype "passive"))
      (node (ref "L3") (pin "1") (pinfunction "1_1") (pintype "passive"))
      (node (ref "R1") (pin "1") (pinfunction "1_1") (pintype "passive"))
      (node (ref "U1") (pin "17") (pinfunction "VCC1_17") (pintype "bidirectional"))
      (node (ref "U1") (pin "38") (pinfunction "VCC2_38") (pintype "bidirectional"))
      (node (ref "U1") (pin "5") (pinfunction "VCC_5") (pintype "power_in"))
    )
    (net (code "3") (name "/2V_REF") (class "Default")
      (node (ref "C36") (pin "1") (pinfunction "1_1") (pintype "passive"))
      (node (ref "IC4") (pin "3") (pinfunction "+IN_3") (pintype "input"))
      (node (ref "R6") (pin "1") (pinfunction "1_1") (pintype "passive"))
      (node (ref "R7") (pin "2") (pinfunction "2_2") (pintype "passive"))
    )
    (net (code "4") (name "/4V_REF_ADC") (class "Default")
      (node (ref "C5") (pin "1") (pinfunction "1_1") (pintype "passive"))
      (node (ref "C6") (pin "+") (pinfunction "+_+") (pintype "passive"))
      (node (ref "R3") (pin "1") (pinfunction "1_1") (pintype "passive"))
      (node (ref "R4") (pin "2") (pinfunction "2_2") (pintype "passive"))
      (node (ref "R6") (pin "2") (pinfunction "2_2") (pintype "passive"))
      (node (ref "SR1") (pin "1") (pinfunction "C_1") (pintype "input"))
      (node (ref "U1") (pin "29") (pinfunction "AREF_29") (pintype "power_in"))
    )
    (net (code "5") (name "/ADC0") (class "Default")
      (node (ref "C10") (pin "1") (pinfunction "1_1") (pintype "passive"))
      (node (ref "R10") (pin "1") (pinfunction "1_1") (pintype "passive"))
      (node (ref "U1") (pin "37") (pinfunction "(ADC0)PA0_37") (pintype "bidirectional"))
    )
    (net (code "6") (name "/ADC1") (class "Default")
      (node (ref "C9") (pin "1") (pinfunction "1_1") (pintype "passive"))
      (node (ref "R9") (pin "1") (pinfunction "1_1") (pintype "passive"))
      (node (ref "U1") (pin "36") (pinfunction "(ADC1)PA1_36") (pintype "bidirectional"))
    )
    (net (code "7") (name "/CH1_IN+") (class "Default")
      (node (ref "CH1_IN+") (pin "2") (pinfunction "2_2") (pintype "bidirectional"))
      (node (ref "PGS2") (pin "1") (pinfunction "1_1") (pintype "input"))
      (node (ref "R22") (pin "1") (pinfunction "1_1") (pintype "passive"))
    )
    (net (code "8") (name "/CH1_IN-") (class "Default")
      (node (ref "CH1_IN-") (pin "2") (pinfunction "2_2") (pintype "bidirectional"))
      (node (ref "PGS1") (pin "2") (pinfunction "2_2") (pintype "input"))
      (node (ref "R21") (pin "1") (pinfunction "1_1") (pintype "passive"))
    )
    (net (code "9") (name "/CH2_IN+") (class "Default")
      (node (ref "CH2_IN+") (pin "2") (pinfunction "2_2") (pintype "bidirectional"))
      (node (ref "PGS4") (pin "1") (pinfunction "1_1") (pintype "input"))
      (node (ref "R28") (pin "1") (pinfunction "1_1") (pintype "passive"))
    )
    (net (code "10") (name "/DRL") (class "Default")
      (node (ref "DRL") (pin "2") (pinfunction "2_2") (pintype "bidirectional"))
      (node (ref "PGS5") (pin "2") (pinfunction "2_2") (pintype "input"))
      (node (ref "R56") (pin "1") (pinfunction "1_1") (pintype "passive"))
    )
    (net (code "11") (name "/PD5") (class "Default")
      (node (ref "R20") (pin "2") (pinfunction "2_2") (pintype "passive"))
      (node (ref "U1") (pin "14") (pinfunction "(OC1A)PD5_14") (pintype "bidirectional"))
    )
    (net (code "12") (name "/RST") (class "Default")
      (node (ref "AVR-ISP") (pin "5") (pinfunction "5_5") (pintype "passive"))
      (node (ref "C1") (pin "1") (pinfunction "1_1") (pintype "passive"))
      (node (ref "R1") (pin "2") (pinfunction "2_2") (pintype "passive"))
      (node (ref "U1") (pin "4") (pinfunction "RESET_4") (pintype "input"))
    )
    (net (code "13") (name "GNDA") (class "Default")
      (node (ref "C10") (pin "2") (pinfunction "2_2") (pintype "passive"))
      (node (ref "C14") (pin "2") (pinfunction "2_2") (pintype "passive"))
      (node (ref "C15") (pin "2") (pinfunction "2_2") (pintype "passive"))
      (node (ref "C16") (pin "2") (pinfunction "2_2") (pintype "passive"))
      (node (ref "C17") (pin "2") (pinfunction "2_2") (pintype "passive"))
      (node (ref "C27") (pin "2") (pinfunction "2_2") (pintype "passive"))
      (node (ref "C28") (pin "2") (pinfunction "2_2") (pintype "passive"))
      (node (ref "C29") (pin "-") (pinfunction "-_-") (pintype "passive"))
      (node (ref "C31") (pin "2") (pinfunction "2_2") (pintype "passive"))
      (node (ref "C32") (pin "-") (pinfunction "-_-") (pintype "passive"))
      (node (ref "C33") (pin "2") (pinfunction "2_2") (pintype "passive"))
      (node (ref "C34") (pin "2") (pinfunction "2_2") (pintype "passive"))
      (node (ref "C35") (pin "-") (pinfunction "-_-") (pintype "passive"))
      (node (ref "C36") (pin "2") (pinfunction "2_2") (pintype "passive"))
      (node (ref "C39") (pin "1") (pinfunction "1_1") (pintype "passive"))
      (node (ref "C4") (pin "2") (pinfunction "2_2") (pintype "passive"))
      (node (ref "C40") (pin "2") (pinfunction "2_2") (pintype "passive"))
      (node (ref "C41") (pin "1") (pinfunction "1_1") (pintype "passive"))
      (node (ref "C42") (pin "2") (pinfunction "2_2") (pintype "passive"))
      (node (ref "C45") (pin "2") (pinfunction "2_2") (pintype "passive"))
      (node (ref "C47") (pin "1") (pinfunction "1_1") (pintype "passive"))
      (node (ref "C48") (pin "2") (pinfunction "2_2") (pintype "passive"))
      (node (ref "C5") (pin "2") (pinfunction "2_2") (pintype "passive"))
      (node (ref "C50") (pin "1") (pinfunction "1_1") (pintype "passive"))
      (node (ref "C6") (pin "-") (pinfunction "-_-") (pintype "passive"))
      (node (ref "C63") (pin "2") (pinfunction "2_2") (pintype "passive"))
      (node (ref "C65") (pin "1") (pinfunction "1_1") (pintype "passive"))
      (node (ref "C66") (pin "2") (pinfunction "2_2") (pintype "passive"))
      (node (ref "C68") (pin "1") (pinfunction "1_1") (pintype "passive"))
      (node (ref "C70") (pin "2") (pinfunction "2_2") (pintype "passive"))
      (node (ref "C71") (pin "1") (pinfunction "1_1") (pintype "passive"))
      (node (ref "C9") (pin "2") (pinfunction "2_2") (pintype "passive"))
      (node (ref "CH1_IN+") (pin "1") (pinfunction "1_1") (pintype "bidirectional"))
      (node (ref "CH1_IN+") (pin "5") (pinfunction "5_5") (pintype "bidirectional"))
      (node (ref "CH1_IN-") (pin "1") (pinfunction "1_1") (pintype "bidirectional"))
      (node (ref "CH1_IN-") (pin "5") (pinfunction "5_5") (pintype "bidirectional"))
      (node (ref "CH2_IN+") (pin "1") (pinfunction "1_1") (pintype "bidirectional"))
      (node (ref "CH2_IN+") (pin "5") (pinfunction "5_5") (pintype "bidirectional"))
      (node (ref "CH2_IN-") (pin "1") (pinfunction "1_1") (pintype "bidirectional"))
      (node (ref "CH2_IN-") (pin "5") (pinfunction "5_5") (pintype "bidirectional"))
      (node (ref "D1") (pin "2") (pinfunction "A_2") (pintype "passive"))
      (node (ref "D2") (pin "2") (pinfunction "A_2") (pintype "passive"))
      (node (ref "D3") (pin "2") (pinfunction "A_2") (pintype "passive"))
      (node (ref "D4") (pin "2") (pinfunction "A_2") (pintype "passive"))
      (node (ref "D5") (pin "2") (pinfunction "A_2") (pintype "passive"))
      (node (ref "DRL") (pin "1") (pinfunction "1_1") (pintype "bidirectional"))
      (node (ref "DRL") (pin "3") (pinfunction "3_3") (pintype "bidirectional"))
      (node (ref "DRL") (pin "5") (pinfunction "5_5") (pintype "bidirectional"))
      (node (ref "DRL-OUT") (pin "1") (pinfunction "1_1") (pintype "passive"))
      (node (ref "IC1") (pin "4") (pinfunction "V-_4") (pintype "power_in"))
      (node (ref "IC2") (pin "4") (pinfunction "V-_4") (pintype "power_in"))
      (node (ref "IC3") (pin "4") (pinfunction "V-_4") (pintype "power_in"))
      (node (ref "IC4") (pin "4") (pinfunction "V-_4") (pintype "power_in"))
      (node (ref "IC5") (pin "4") (pinfunction "V-_4") (pintype "power_in"))
      (node (ref "IC6") (pin "4") (pinfunction "V-_4") (pintype "power_in"))
      (node (ref "PGS1") (pin "1") (pinfunction "1_1") (pintype "input"))
      (node (ref "PGS2") (pin "2") (pinfunction "2_2") (pintype "input"))
      (node (ref "PGS3") (pin "1") (pinfunction "1_1") (pintype "input"))
      (node (ref "PGS4") (pin "2") (pinfunction "2_2") (pintype "input"))
      (node (ref "PGS5") (pin "1") (pinfunction "1_1") (pintype "input"))
      (node (ref "PWR") (pin "K") (pinfunction "C_K") (pintype "passive"))
      (node (ref "R5") (pin "1") (pinfunction "1_1") (pintype "passive"))
      (node (ref "R52") (pin "1") (pinfunction "1_1") (pintype "passive"))
      (node (ref "R7") (pin "1") (pinfunction "1_1") (pintype "passive"))
      (node (ref "SR1") (pin "3") (pinfunction "A_3") (pintype "input"))
      (node (ref "TR3") (pin "3") (pinfunction "3_3") (pintype "passive"))
      (node (ref "U1") (pin "28") (pinfunction "AGND_28") (pintype "power_in"))
      (node (ref "XT-CON") (pin "11") (pinfunction "S_11") (pintype "passive"))
      (node (ref "XT-CON") (pin "13") (pinfunction "S_13") (pintype "passive"))
      (node (ref "XT-CON") (pin "2") (pinfunction "S_2") (pintype "passive"))
      (node (ref "XT-CON") (pin "4") (pinfunction "S_4") (pintype "passive"))
      (node (ref "XT-CON") (pin "6") (pinfunction "S_6") (pintype "passive"))
      (node (ref "XT-CON") (pin "8") (pinfunction "S_8") (pintype "passive"))
      (node (ref "Z1") (pin "2") (pinfunction "A_2") (pintype "passive"))
    )
    (net (code "14") (name "Net-(C55-Pad2)") (class "Default")
      (node (ref "C55") (pin "2") (pinfunction "2_2") (pintype "passive"))
      (node (ref "R42") (pin "1") (pinfunction "1_1") (pintype "passive"))
      (node (ref "R44") (pin "1") (pinfunction "1_1") (pintype "passive"))
    )
    (net (code "15") (name "Net-(C56-Pad2)") (class "Default")
      (node (ref "C56") (pin "2") (pinfunction "2_2") (pintype "passive"))
      (node (ref "R43") (pin "1") (pinfunction "1_1") (pintype "passive"))
      (node (ref "R45") (pin "1") (pinfunction "1_1") (pintype "passive"))
    )
    (net (code "16") (name "Net-(C57-Pad1)") (class "Default")
      (node (ref "C57") (pin "1") (pinfunction "1_1") (pintype "passive"))
      (node (ref "R44") (pin "2") (pinfunction "2_2") (pintype "passive"))
      (node (ref "R46") (pin "1") (pinfunction "1_1") (pintype "passive"))
    )
    (net (code "17") (name "Net-(C58-Pad1)") (class "Default")
      (node (ref "C58") (pin "1") (pinfunction "1_1") (pintype "passive"))
      (node (ref "R45") (pin "2") (pinfunction "2_2") (pintype "passive"))
      (node (ref "R47") (pin "1") (pinfunction "1_1") (pintype "passive"))
    )
    (net (code "18") (name "Net-(CAL-Pad1)") (class "Default")
      (node (ref "CAL") (pin "1") (pinfunction "1_1") (pintype "passive"))
      (node (ref "R18") (pin "1") (pinfunction "1_1") (pintype "passive"))
    )
    (net (code "19") (name "Net-(CAL-Pad2)") (class "Default")
      (node (ref "CAL") (pin "2") (pinfunction "2_2") (pintype "passive"))
      (node (ref "R16") (pin "1") (pinfunction "1_1") (pintype "passive"))
    )
    (net (code "20") (name "Net-(CH1_IN+-Pad3)") (class "Default")
      (node (ref "CH1_IN+") (pin "3") (pinfunction "3_3") (pintype "bidirectional"))
      (node (ref "R58") (pin "1") (pinfunction "1_1") (pintype "passive"))
    )
    (net (code "21") (name "Net-(CH1_IN--Pad3)") (class "Default")
      (node (ref "CH1_IN-") (pin "3") (pinfunction "3_3") (pintype "bidirectional"))
      (node (ref "R57") (pin "1") (pinfunction "1_1") (pintype "passive"))
    )
    (net (code "22") (name "Net-(CH2_IN+-Pad3)") (class "Default")
      (node (ref "CH2_IN+") (pin "3") (pinfunction "3_3") (pintype "bidirectional"))
      (node (ref "R60") (pin "1") (pinfunction "1_1") (pintype "passive"))
    )
    (net (code "23") (name "Net-(CH2_IN--Pad2)") (class "Default")
      (node (ref "CH2_IN-") (pin "2") (pinfunction "2_2") (pintype "bidirectional"))
      (node (ref "PGS3") (pin "2") (pinfunction "2_2") (pintype "input"))
      (node (ref "R27") (pin "1") (pinfunction "1_1") (pintype "passive"))
    )
    (net (code "24") (name "Net-(CH2_IN--Pad3)") (class "Default")
      (node (ref "CH2_IN-") (pin "3") (pinfunction "3_3") (pintype "bidirectional"))
      (node (ref "R59") (pin "1") (pinfunction "1_1") (pintype "passive"))
    )
    (net (code "25") (name "Net-(D1-AK)") (class "Default")
      (node (ref "C37") (pin "2") (pinfunction "2_2") (pintype "passive"))
      (node (ref "C39") (pin "2") (pinfunction "2_2") (pintype "passive"))
      (node (ref "D1") (pin "3") (pinfunction "AK_3") (pintype "passive"))
      (node (ref "R21") (pin "2") (pinfunction "2_2") (pintype "passive"))
      (node (ref "R23") (pin "2") (pinfunction "2_2") (pintype "passive"))
      (node (ref "R8") (pin "2") (pinfunction "2_2") (pintype "passive"))
    )
    (net (code "26") (name "Net-(D2-AK)") (class "Default")
      (node (ref "C37") (pin "1") (pinfunction "1_1") (pintype "passive"))
      (node (ref "C40") (pin "1") (pinfunction "1_1") (pintype "passive"))
      (node (ref "D2") (pin "3") (pinfunction "AK_3") (pintype "passive"))
      (node (ref "R22") (pin "2") (pinfunction "2_2") (pintype "passive"))
      (node (ref "R26") (pin "2") (pinfunction "2_2") (pintype "passive"))
      (node (ref "R53") (pin "2") (pinfunction "2_2") (pintype "passive"))
    )
    (net (code "27") (name "Net-(D3-AK)") (class "Default")
      (node (ref "C38") (pin "2") (pinfunction "2_2") (pintype "passive"))
      (node (ref "C41") (pin "2") (pinfunction "2_2") (pintype "passive"))
      (node (ref "D3") (pin "3") (pinfunction "AK_3") (pintype "passive"))
      (node (ref "R27") (pin "2") (pinfunction "2_2") (pintype "passive"))
      (node (ref "R29") (pin "2") (pinfunction "2_2") (pintype "passive"))
      (node (ref "R54") (pin "2") (pinfunction "2_2") (pintype "passive"))
    )
    (net (code "28") (name "Net-(D4-AK)") (class "Default")
      (node (ref "C38") (pin "1") (pinfunction "1_1") (pintype "passive"))
      (node (ref "C42") (pin "1") (pinfunction "1_1") (pintype "passive"))
      (node (ref "D4") (pin "3") (pinfunction "AK_3") (pintype "passive"))
      (node (ref "R28") (pin "2") (pinfunction "2_2") (pintype "passive"))
      (node (ref "R32") (pin "2") (pinfunction "2_2") (pintype "passive"))
      (node (ref "R55") (pin "2") (pinfunction "2_2") (pintype "passive"))
    )
    (net (code "29") (name "Net-(D5-AK)") (class "Default")
      (node (ref "C43") (pin "2") (pinfunction "2_2") (pintype "passive"))
      (node (ref "C44") (pin "2") (pinfunction "2_2") (pintype "passive"))
      (node (ref "D5") (pin "3") (pinfunction "AK_3") (pintype "passive"))
      (node (ref "R35") (pin "1") (pinfunction "1_1") (pintype "passive"))
      (node (ref "R56") (pin "2") (pinfunction "2_2") (pintype "passive"))
    )
    (net (code "30") (name "Net-(IC1A-+IN)") (class "Default")
      (node (ref "C51") (pin "2") (pinfunction "2_2") (pintype "passive"))
      (node (ref "IC1") (pin "3") (pinfunction "+IN_3") (pintype "input"))
      (node (ref "R36") (pin "1") (pinfunction "1_1") (pintype "passive"))
    )
    (net (code "31") (name "Net-(IC1A--IN)") (class "Default")
      (node (ref "C53") (pin "1") (pinfunction "1_1") (pintype "passive"))
      (node (ref "IC1") (pin "2") (pinfunction "-IN_2") (pintype "input"))
      (node (ref "R38") (pin "1") (pinfunction "1_1") (pintype "passive"))
      (node (ref "R40") (pin "1") (pinfunction "1_1") (pintype "passive"))
    )
    (net (code "32") (name "Net-(IC1A-OUT)") (class "Default")
      (node (ref "C53") (pin "2") (pinfunction "2_2") (pintype "passive"))
      (node (ref "C55") (pin "1") (pinfunction "1_1") (pintype "passive"))
      (node (ref "IC1") (pin "1") (pinfunction "OUT_1") (pintype "output"))
      (node (ref "R38") (pin "2") (pinfunction "2_2") (pintype "passive"))
    )
    (net (code "33") (name "Net-(IC1B-+IN)") (class "Default")
      (node (ref "C59") (pin "1") (pinfunction "1_1") (pintype "passive"))
      (node (ref "IC1") (pin "5") (pinfunction "+IN_5") (pintype "input"))
      (node (ref "R46") (pin "2") (pinfunction "2_2") (pintype "passive"))
    )
    (net (code "34") (name "Net-(IC1B--IN)") (class "Default")
      (node (ref "C61") (pin "1") (pinfunction "1_1") (pintype "passive"))
      (node (ref "IC1") (pin "6") (pinfunction "-IN_6") (pintype "input"))
      (node (ref "R48") (pin "1") (pinfunction "1_1") (pintype "passive"))
      (node (ref "R50") (pin "1") (pinfunction "1_1") (pintype "passive"))
    )
    (net (code "35") (name "Net-(IC1B-OUT)") (class "Default")
      (node (ref "C57") (pin "2") (pinfunction "2_2") (pintype "passive"))
      (node (ref "C61") (pin "2") (pinfunction "2_2") (pintype "passive"))
      (node (ref "IC1") (pin "7") (pinfunction "OUT_7") (pintype "output"))
      (node (ref "R10") (pin "2") (pinfunction "2_2") (pintype "passive"))
      (node (ref "R50") (pin "2") (pinfunction "2_2") (pintype "passive"))
    )
    (net (code "36") (name "Net-(IC2A-+IN)") (class "Default")
      (node (ref "C52") (pin "2") (pinfunction "2_2") (pintype "passive"))
      (node (ref "IC2") (pin "3") (pinfunction "+IN_3") (pintype "input"))
      (node (ref "R37") (pin "1") (pinfunction "1_1") (pintype "passive"))
    )
    (net (code "37") (name "Net-(IC2A--IN)") (class "Default")
      (node (ref "C54") (pin "1") (pinfunction "1_1") (pintype "passive"))
      (node (ref "IC2") (pin "2") (pinfunction "-IN_2") (pintype "input"))
      (node (ref "R39") (pin "1") (pinfunction "1_1") (pintype "passive"))
      (node (ref "R41") (pin "1") (pinfunction "1_1") (pintype "passive"))
    )
    (net (code "38") (name "Net-(IC2A-OUT)") (class "Default")
      (node (ref "C54") (pin "2") (pinfunction "2_2") (pintype "passive"))
      (node (ref "C56") (pin "1") (pinfunction "1_1") (pintype "passive"))
      (node (ref "IC2") (pin "1") (pinfunction "OUT_1") (pintype "output"))
      (node (ref "R39") (pin "2") (pinfunction "2_2") (pintype "passive"))
    )
    (net (code "39") (name "Net-(IC2B-+IN)") (class "Default")
      (node (ref "C60") (pin "1") (pinfunction "1_1") (pintype "passive"))
      (node (ref "IC2") (pin "5") (pinfunction "+IN_5") (pintype "input"))
      (node (ref "R47") (pin "2") (pinfunction "2_2") (pintype "passive"))
    )
    (net (code "40") (name "Net-(IC2B--IN)") (class "Default")
      (node (ref "C62") (pin "1") (pinfunction "1_1") (pintype "passive"))
      (node (ref "IC2") (pin "6") (pinfunction "-IN_6") (pintype "input"))
      (node (ref "R49") (pin "1") (pinfunction "1_1") (pintype "passive"))
      (node (ref "R51") (pin "1") (pinfunction "1_1") (pintype "passive"))
    )
    (net (code "41") (name "Net-(IC2B-OUT)") (class "Default")
      (node (ref "C58") (pin "2") (pinfunction "2_2") (pintype "passive"))
      (node (ref "C62") (pin "2") (pinfunction "2_2") (pintype "passive"))
      (node (ref "IC2") (pin "7") (pinfunction "OUT_7") (pintype "output"))
      (node (ref "R51") (pin "2") (pinfunction "2_2") (pintype "passive"))
      (node (ref "R9") (pin "2") (pinfunction "2_2") (pintype "passive"))
    )
    (net (code "42") (name "Net-(IC3A-+IN)") (class "Default")
      (node (ref "IC3") (pin "3") (pinfunction "+IN_3") (pintype "input"))
      (node (ref "R30") (pin "2") (pinfunction "2_2") (pintype "passive"))
      (node (ref "R31") (pin "2") (pinfunction "2_2") (pintype "passive"))
    )
    (net (code "43") (name "Net-(IC3A--IN)") (class "Default")
      (node (ref "IC3") (pin "1") (pinfunction "OUT_1") (pintype "output"))
      (node (ref "IC3") (pin "2") (pinfunction "-IN_2") (pintype "input"))
      (node (ref "R34") (pin "2") (pinfunction "2_2") (pintype "passive"))
    )
    (net (code "44") (name "Net-(IC3B-+IN)") (class "Default")
      (node (ref "IC3") (pin "5") (pinfunction "+IN_5") (pintype "input"))
      (node (ref "R24") (pin "2") (pinfunction "2_2") (pintype "passive"))
      (node (ref "R25") (pin "2") (pinfunction "2_2") (pintype "passive"))
    )
    (net (code "45") (name "Net-(IC3B--IN)") (class "Default")
      (node (ref "IC3") (pin "6") (pinfunction "-IN_6") (pintype "input"))
      (node (ref "IC3") (pin "7") (pinfunction "OUT_7") (pintype "output"))
      (node (ref "R33") (pin "2") (pinfunction "2_2") (pintype "passive"))
    )
    (net (code "46") (name "Net-(IC4B-+IN)") (class "Default")
      (node (ref "IC4") (pin "5") (pinfunction "+IN_5") (pintype "input"))
      (node (ref "TR3") (pin "2") (pinfunction "2_2") (pintype "passive"))
      (node (ref "TR3_DIS") (pin "1") (pinfunction "1_1") (pintype "passive"))
    )
    (net (code "47") (name "Net-(IC4B--IN)") (class "Default")
      (node (ref "C43") (pin "1") (pinfunction "1_1") (pintype "passive"))
      (node (ref "DRL-OUT") (pin "3") (pinfunction "3_3") (pintype "passive"))
      (node (ref "IC4") (pin "6") (pinfunction "-IN_6") (pintype "input"))
      (node (ref "R33") (pin "1") (pinfunction "1_1") (pintype "passive"))
      (node (ref "R34") (pin "1") (pinfunction "1_1") (pintype "passive"))
      (node (ref "XT-CON") (pin "12") (pinfunction "S_12") (pintype "passive"))
    )
    (net (code "48") (name "Net-(IC4B-OUT)") (class "Default")
      (node (ref "C44") (pin "1") (pinfunction "1_1") (pintype "passive"))
      (node (ref "IC4") (pin "7") (pinfunction "OUT_7") (pintype "output"))
      (node (ref "R35") (pin "2") (pinfunction "2_2") (pintype "passive"))
    )
    (net (code "49") (name "Net-(IC5-+IN)") (class "Default")
      (node (ref "IC5") (pin "3") (pinfunction "+IN_3") (pintype "input"))
      (node (ref "R26") (pin "1") (pinfunction "1_1") (pintype "passive"))
    )
    (net (code "50") (name "Net-(IC5--IN)") (class "Default")
      (node (ref "IC5") (pin "2") (pinfunction "-IN_2") (pintype "input"))
      (node (ref "R23") (pin "1") (pinfunction "1_1") (pintype "passive"))
    )
    (net (code "51") (name "Net-(IC5-OUT)") (class "Default")
      (node (ref "C51") (pin "1") (pinfunction "1_1") (pintype "passive"))
      (node (ref "IC5") (pin "6") (pinfunction "OUT_6") (pintype "output"))
    )
    (net (code "52") (name "Net-(IC5-RG-Pad1)") (class "Default")
      (node (ref "IC5") (pin "1") (pinfunction "RG_1") (pintype "passive"))
      (node (ref "R24") (pin "1") (pinfunction "1_1") (pintype "passive"))
    )
    (net (code "53") (name "Net-(IC5-RG-Pad8)") (class "Default")
      (node (ref "IC5") (pin "8") (pinfunction "RG_8") (pintype "passive"))
      (node (ref "R25") (pin "1") (pinfunction "1_1") (pintype "passive"))
    )
    (net (code "54") (name "Net-(IC6-+IN)") (class "Default")
      (node (ref "IC6") (pin "3") (pinfunction "+IN_3") (pintype "input"))
      (node (ref "R32") (pin "1") (pinfunction "1_1") (pintype "passive"))
    )
    (net (code "55") (name "Net-(IC6--IN)") (class "Default")
      (node (ref "IC6") (pin "2") (pinfunction "-IN_2") (pintype "input"))
      (node (ref "R29") (pin "1") (pinfunction "1_1") (pintype "passive"))
    )
    (net (code "56") (name "Net-(IC6-OUT)") (class "Default")
      (node (ref "C52") (pin "1") (pinfunction "1_1") (pintype "passive"))
      (node (ref "IC6") (pin "6") (pinfunction "OUT_6") (pintype "output"))
    )
    (net (code "57") (name "Net-(IC6-RG-Pad1)") (class "Default")
      (node (ref "IC6") (pin "1") (pinfunction "RG_1") (pintype "passive"))
      (node (ref "R30") (pin "1") (pinfunction "1_1") (pintype "passive"))
    )
    (net (code "58") (name "Net-(IC6-RG-Pad8)") (class "Default")
      (node (ref "IC6") (pin "8") (pinfunction "RG_8") (pintype "passive"))
      (node (ref "R31") (pin "1") (pinfunction "1_1") (pintype "passive"))
    )
    (net (code "59") (name "Net-(PWR-PadA)") (class "Default")
      (node (ref "PWR") (pin "A") (pinfunction "A_A") (pintype "passive"))
      (node (ref "R62") (pin "1") (pinfunction "1_1") (pintype "passive"))
    )
    (net (code "60") (name "Net-(R16-Pad2)") (class "Default")
      (node (ref "R16") (pin "2") (pinfunction "2_2") (pintype "passive"))
      (node (ref "R17") (pin "2") (pinfunction "2_2") (pintype "passive"))
      (node (ref "R19") (pin "1") (pinfunction "1_1") (pintype "passive"))
    )
    (net (code "61") (name "Net-(R19-Pad2)") (class "Default")
      (node (ref "R19") (pin "2") (pinfunction "2_2") (pintype "passive"))
      (node (ref "R20") (pin "1") (pinfunction "1_1") (pintype "passive"))
    )
    (net (code "62") (name "Net-(R40-Pad2)") (class "Default")
      (node (ref "R40") (pin "2") (pinfunction "2_2") (pintype "passive"))
      (node (ref "TR1") (pin "1") (pinfunction "1_1") (pintype "passive"))
    )
    (net (code "63") (name "Net-(R41-Pad2)") (class "Default")
      (node (ref "R41") (pin "2") (pinfunction "2_2") (pintype "passive"))
      (node (ref "TR2") (pin "1") (pinfunction "1_1") (pintype "passive"))
    )
    (net (code "64") (name "Net-(SR1-R)") (class "Default")
      (node (ref "R4") (pin "1") (pinfunction "1_1") (pintype "passive"))
      (node (ref "R5") (pin "2") (pinfunction "2_2") (pintype "passive"))
      (node (ref "SR1") (pin "2") (pinfunction "R_2") (pintype "input"))
    )
    (net (code "65") (name "Net-(TCK-PP)") (class "Default")
      (node (ref "TCK") (pin "P$1") (pinfunction "PP_P$1") (pintype "passive"))
      (node (ref "U1") (pin "21") (pinfunction "PC2(TCK)_21") (pintype "bidirectional"))
    )
    (net (code "66") (name "Net-(TDI-PP)") (class "Default")
      (node (ref "TDI") (pin "P$1") (pinfunction "PP_P$1") (pintype "passive"))
      (node (ref "U1") (pin "24") (pinfunction "PC5(TDI)_24") (pintype "bidirectional"))
    )
    (net (code "67") (name "Net-(TDO-PP)") (class "Default")
      (node (ref "TDO") (pin "P$1") (pinfunction "PP_P$1") (pintype "passive"))
      (node (ref "U1") (pin "23") (pinfunction "PC4(TDO)_23") (pintype "bidirectional"))
    )
    (net (code "68") (name "Net-(TMS-PP)") (class "Default")
      (node (ref "TMS") (pin "P$1") (pinfunction "PP_P$1") (pintype "passive"))
      (node (ref "U1") (pin "22") (pinfunction "PC3(TMS)_22") (pintype "bidirectional"))
    )
    (net (code "69") (name "Net-(U1-(ADC2)PA2)") (class "Default")
      (node (ref "C17") (pin "1") (pinfunction "1_1") (pintype "passive"))
      (node (ref "R63") (pin "1") (pinfunction "1_1") (pintype "passive"))
      (node (ref "U1") (pin "35") (pinfunction "(ADC2)PA2_35") (pintype "bidirectional"))
    )
    (net (code "70") (name "Net-(U1-(ADC3)PA3)") (class "Default")
      (node (ref "C16") (pin "1") (pinfunction "1_1") (pintype "passive"))
      (node (ref "R15") (pin "1") (pinfunction "1_1") (pintype "passive"))
      (node (ref "U1") (pin "34") (pinfunction "(ADC3)PA3_34") (pintype "bidirectional"))
    )
    (net (code "71") (name "Net-(U1-(ADC4)PA4)") (class "Default")
      (node (ref "C15") (pin "1") (pinfunction "1_1") (pintype "passive"))
      (node (ref "R14") (pin "1") (pinfunction "1_1") (pintype "passive"))
      (node (ref "U1") (pin "33") (pinfunction "(ADC4)PA4_33") (pintype "bidirectional"))
    )
    (net (code "72") (name "Net-(U1-(ADC5)PA5)") (class "Default")
      (node (ref "C14") (pin "1") (pinfunction "1_1") (pintype "passive"))
      (node (ref "R13") (pin "1") (pinfunction "1_1") (pintype "passive"))
      (node (ref "U1") (pin "32") (pinfunction "(ADC5)PA5_32") (pintype "bidirectional"))
    )
    (net (code "73") (name "Net-(U1-(MISO)PB6)") (class "Default")
      (node (ref "AVR-ISP") (pin "1") (pinfunction "1_1") (pintype "passive"))
      (node (ref "U1") (pin "2") (pinfunction "(MISO)PB6_2") (pintype "bidirectional"))
    )
    (net (code "74") (name "Net-(U1-(MOSI)PB5)") (class "Default")
      (node (ref "AVR-ISP") (pin "4") (pinfunction "4_4") (pintype "passive"))
      (node (ref "U1") (pin "1") (pinfunction "(MOSI)PB5_1") (pintype "bidirectional"))
    )
    (net (code "75") (name "Net-(U1-(RXD)PD0)") (class "Default")
      (node (ref "P/C-CON") (pin "6") (pinfunction "6_6") (pintype "passive"))
      (node (ref "U1") (pin "9") (pinfunction "(RXD)PD0_9") (pintype "bidirectional"))
    )
    (net (code "76") (name "Net-(U1-(SCK)PB7)") (class "Default")
      (node (ref "AVR-ISP") (pin "3") (pinfunction "3_3") (pintype "passive"))
      (node (ref "U1") (pin "3") (pinfunction "(SCK)PB7_3") (pintype "bidirectional"))
    )
    (net (code "77") (name "Net-(U1-(TXD)PD1)") (class "Default")
      (node (ref "P/C-CON") (pin "4") (pinfunction "4_4") (pintype "passive"))
      (node (ref "U1") (pin "10") (pinfunction "(TXD)PD1_10") (pintype "bidirectional"))
    )
    (net (code "78") (name "Net-(U1-AVCC)") (class "Default")
      (node (ref "C4") (pin "1") (pinfunction "1_1") (pintype "passive"))
      (node (ref "R2") (pin "1") (pinfunction "1_1") (pintype "passive"))
      (node (ref "U1") (pin "27") (pinfunction "AVCC_27") (pintype "power_in"))
    )
    (net (code "79") (name "Net-(U1-XTAL1)") (class "Default")
      (node (ref "C3") (pin "1") (pinfunction "1_1") (pintype "passive"))
      (node (ref "Q1") (pin "2") (pinfunction "2_2") (pintype "passive"))
      (node (ref "U1") (pin "8") (pinfunction "XTAL1_8") (pintype "bidirectional"))
    )
    (net (code "80") (name "Net-(U1-XTAL2)") (class "Default")
      (node (ref "C2") (pin "1") (pinfunction "1_1") (pintype "passive"))
      (node (ref "Q1") (pin "1") (pinfunction "1_1") (pintype "passive"))
      (node (ref "U1") (pin "7") (pinfunction "XTAL2_7") (pintype "bidirectional"))
    )
    (net (code "81") (name "Net-(XT-CONA-S)") (class "Default")
      (node (ref "R13") (pin "2") (pinfunction "2_2") (pintype "passive"))
      (node (ref "XT-CON") (pin "1") (pinfunction "S_1") (pintype "passive"))
    )
    (net (code "82") (name "Net-(XT-CONH-S)") (class "Default")
      (node (ref "R14") (pin "2") (pinfunction "2_2") (pintype "passive"))
      (node (ref "XT-CON") (pin "3") (pinfunction "S_3") (pintype "passive"))
    )
    (net (code "83") (name "Net-(XT-CONJ-S)") (class "Default")
      (node (ref "R15") (pin "2") (pinfunction "2_2") (pintype "passive"))
      (node (ref "XT-CON") (pin "5") (pinfunction "S_5") (pintype "passive"))
    )
    (net (code "84") (name "Net-(XT-CONL-S)") (class "Default")
      (node (ref "R63") (pin "2") (pinfunction "2_2") (pintype "passive"))
      (node (ref "XT-CON") (pin "7") (pinfunction "S_7") (pintype "passive"))
    )
    (net (code "85") (name "PE") (class "Default")
      (node (ref "AVR-ISP") (pin "6") (pinfunction "6_6") (pintype "passive"))
      (node (ref "C1") (pin "2") (pinfunction "2_2") (pintype "passive"))
      (node (ref "C2") (pin "2") (pinfunction "2_2") (pintype "passive"))
      (node (ref "C24") (pin "2") (pinfunction "2_2") (pintype "passive"))
      (node (ref "C25") (pin "2") (pinfunction "2_2") (pintype "passive"))
      (node (ref "C26") (pin "-") (pinfunction "-_-") (pintype "passive"))
      (node (ref "C3") (pin "2") (pinfunction "2_2") (pintype "passive"))
      (node (ref "C7") (pin "2") (pinfunction "2_2") (pintype "passive"))
      (node (ref "C72") (pin "2") (pinfunction "2_2") (pintype "passive"))
      (node (ref "C8") (pin "2") (pinfunction "2_2") (pintype "passive"))
      (node (ref "P/C-CON") (pin "3") (pinfunction "3_3") (pintype "passive"))
      (node (ref "P/C-CON") (pin "5") (pinfunction "5_5") (pintype "passive"))
      (node (ref "R52") (pin "2") (pinfunction "2_2") (pintype "passive"))
      (node (ref "U1") (pin "18") (pinfunction "GND1_18") (pintype "bidirectional"))
      (node (ref "U1") (pin "39") (pinfunction "GND2_39") (pintype "bidirectional"))
      (node (ref "U1") (pin "6") (pinfunction "GND_6") (pintype "power_in"))
    )
    (net (code "86") (name "VIN") (class "Default")
      (node (ref "L2") (pin "1") (pinfunction "1_1") (pintype "passive"))
      (node (ref "P/C-CON") (pin "1") (pinfunction "1_1") (pintype "passive"))
      (node (ref "P/C-CON") (pin "2") (pinfunction "2_2") (pintype "passive"))
      (node (ref "R62") (pin "2") (pinfunction "2_2") (pintype "passive"))
    )
    (net (code "87") (name "V_REF") (class "Default")
      (node (ref "C30") (pin "1") (pinfunction "1_1") (pintype "passive"))
      (node (ref "C31") (pin "1") (pinfunction "1_1") (pintype "passive"))
      (node (ref "C32") (pin "+") (pinfunction "+_+") (pintype "passive"))
      (node (ref "C46") (pin "2") (pinfunction "2_2") (pintype "passive"))
      (node (ref "C47") (pin "2") (pinfunction "2_2") (pintype "passive"))
      (node (ref "C49") (pin "2") (pinfunction "2_2") (pintype "passive"))
      (node (ref "C50") (pin "2") (pinfunction "2_2") (pintype "passive"))
      (node (ref "C59") (pin "2") (pinfunction "2_2") (pintype "passive"))
      (node (ref "C60") (pin "2") (pinfunction "2_2") (pintype "passive"))
      (node (ref "C64") (pin "2") (pinfunction "2_2") (pintype "passive"))
      (node (ref "C65") (pin "2") (pinfunction "2_2") (pintype "passive"))
      (node (ref "C67") (pin "2") (pinfunction "2_2") (pintype "passive"))
      (node (ref "C68") (pin "2") (pinfunction "2_2") (pintype "passive"))
      (node (ref "C69") (pin "2") (pinfunction "2_2") (pintype "passive"))
      (node (ref "C71") (pin "2") (pinfunction "2_2") (pintype "passive"))
      (node (ref "DRL-OUT") (pin "2") (pinfunction "2_2") (pintype "passive"))
      (node (ref "IC4") (pin "1") (pinfunction "OUT_1") (pintype "output"))
      (node (ref "IC4") (pin "2") (pinfunction "-IN_2") (pintype "input"))
      (node (ref "IC5") (pin "5") (pinfunction "REF_5") (pintype "passive"))
      (node (ref "IC6") (pin "5") (pinfunction "REF_5") (pintype "passive"))
      (node (ref "R17") (pin "1") (pinfunction "1_1") (pintype "passive"))
      (node (ref "R18") (pin "2") (pinfunction "2_2") (pintype "passive"))
      (node (ref "R36") (pin "2") (pinfunction "2_2") (pintype "passive"))
      (node (ref "R37") (pin "2") (pinfunction "2_2") (pintype "passive"))
      (node (ref "R42") (pin "2") (pinfunction "2_2") (pintype "passive"))
      (node (ref "R43") (pin "2") (pinfunction "2_2") (pintype "passive"))
      (node (ref "R48") (pin "2") (pinfunction "2_2") (pintype "passive"))
      (node (ref "R49") (pin "2") (pinfunction "2_2") (pintype "passive"))
      (node (ref "R53") (pin "1") (pinfunction "1_1") (pintype "passive"))
      (node (ref "R54") (pin "1") (pinfunction "1_1") (pintype "passive"))
      (node (ref "R55") (pin "1") (pinfunction "1_1") (pintype "passive"))
      (node (ref "R8") (pin "1") (pinfunction "1_1") (pintype "passive"))
      (node (ref "TR1") (pin "2") (pinfunction "2_2") (pintype "passive"))
      (node (ref "TR1") (pin "3") (pinfunction "3_3") (pintype "passive"))
      (node (ref "TR2") (pin "2") (pinfunction "2_2") (pintype "passive"))
      (node (ref "TR2") (pin "3") (pinfunction "3_3") (pintype "passive"))
      (node (ref "TR3") (pin "1") (pinfunction "1_1") (pintype "passive"))
      (node (ref "TR3_DIS") (pin "2") (pinfunction "2_2") (pintype "passive"))
      (node (ref "XT-CON") (pin "14") (pinfunction "S_14") (pintype "passive"))
    )
    (net (code "88") (name "unconnected-(CH1_IN+-Pad4)") (class "Default")
      (node (ref "CH1_IN+") (pin "4") (pinfunction "4_4") (pintype "bidirectional"))
    )
    (net (code "89") (name "unconnected-(CH1_IN--Pad4)") (class "Default")
      (node (ref "CH1_IN-") (pin "4") (pinfunction "4_4") (pintype "bidirectional"))
    )
    (net (code "90") (name "unconnected-(CH2_IN+-Pad4)") (class "Default")
      (node (ref "CH2_IN+") (pin "4") (pinfunction "4_4") (pintype "bidirectional"))
    )
    (net (code "91") (name "unconnected-(CH2_IN--Pad4)") (class "Default")
      (node (ref "CH2_IN-") (pin "4") (pinfunction "4_4") (pintype "bidirectional"))
    )
    (net (code "92") (name "unconnected-(DRL-Pad4)") (class "Default")
      (node (ref "DRL") (pin "4") (pinfunction "4_4") (pintype "bidirectional"))
    )
    (net (code "93") (name "unconnected-(U1-(ADC6)PA6-Pad31)") (class "Default")
      (node (ref "U1") (pin "31") (pinfunction "(ADC6)PA6_31") (pintype "bidirectional"))
    )
    (net (code "94") (name "unconnected-(U1-(ADC7)PA7-Pad30)") (class "Default")
      (node (ref "U1") (pin "30") (pinfunction "(ADC7)PA7_30") (pintype "bidirectional"))
    )
    (net (code "95") (name "unconnected-(U1-(AIN0{slash}INT2)PB2-Pad42)") (class "Default")
      (node (ref "U1") (pin "42") (pinfunction "(AIN0/INT2)PB2_42") (pintype "bidirectional"))
    )
    (net (code "96") (name "unconnected-(U1-(AIN1)PB3-Pad43)") (class "Default")
      (node (ref "U1") (pin "43") (pinfunction "(AIN1)PB3_43") (pintype "bidirectional"))
    )
    (net (code "97") (name "unconnected-(U1-(ICP)PD6-Pad15)") (class "Default")
      (node (ref "U1") (pin "15") (pinfunction "(ICP)PD6_15") (pintype "bidirectional"))
    )
    (net (code "98") (name "unconnected-(U1-(INT0)PD2-Pad11)") (class "Default")
      (node (ref "U1") (pin "11") (pinfunction "(INT0)PD2_11") (pintype "bidirectional"))
    )
    (net (code "99") (name "unconnected-(U1-(INT1)PD3-Pad12)") (class "Default")
      (node (ref "U1") (pin "12") (pinfunction "(INT1)PD3_12") (pintype "bidirectional"))
    )
    (net (code "100") (name "unconnected-(U1-(OC1B)PD4-Pad13)") (class "Default")
      (node (ref "U1") (pin "13") (pinfunction "(OC1B)PD4_13") (pintype "bidirectional"))
    )
    (net (code "101") (name "unconnected-(U1-(OC2)PD7-Pad16)") (class "Default")
      (node (ref "U1") (pin "16") (pinfunction "(OC2)PD7_16") (pintype "bidirectional"))
    )
    (net (code "102") (name "unconnected-(U1-(SS)PB4-Pad44)") (class "Default")
      (node (ref "U1") (pin "44") (pinfunction "(SS)PB4_44") (pintype "bidirectional"))
    )
    (net (code "103") (name "unconnected-(U1-(T0)PB0-Pad40)") (class "Default")
      (node (ref "U1") (pin "40") (pinfunction "(T0)PB0_40") (pintype "bidirectional"))
    )
    (net (code "104") (name "unconnected-(U1-(T1)PB1-Pad41)") (class "Default")
      (node (ref "U1") (pin "41") (pinfunction "(T1)PB1_41") (pintype "bidirectional"))
    )
    (net (code "105") (name "unconnected-(U1-(TOSC1)PC6-Pad25)") (class "Default")
      (node (ref "U1") (pin "25") (pinfunction "(TOSC1)PC6_25") (pintype "bidirectional"))
    )
    (net (code "106") (name "unconnected-(U1-(TOSC2)PC7-Pad26)") (class "Default")
      (node (ref "U1") (pin "26") (pinfunction "(TOSC2)PC7_26") (pintype "bidirectional"))
    )
    (net (code "107") (name "unconnected-(U1-PC0(SCL)-Pad19)") (class "Default")
      (node (ref "U1") (pin "19") (pinfunction "PC0(SCL)_19") (pintype "bidirectional"))
    )
    (net (code "108") (name "unconnected-(U1-PC1(SDA)-Pad20)") (class "Default")
      (node (ref "U1") (pin "20") (pinfunction "PC1(SDA)_20") (pintype "bidirectional"))
    )
  )
)
